# MAIN.net
KiCad netlist of a schematic drawn in Altium Designer
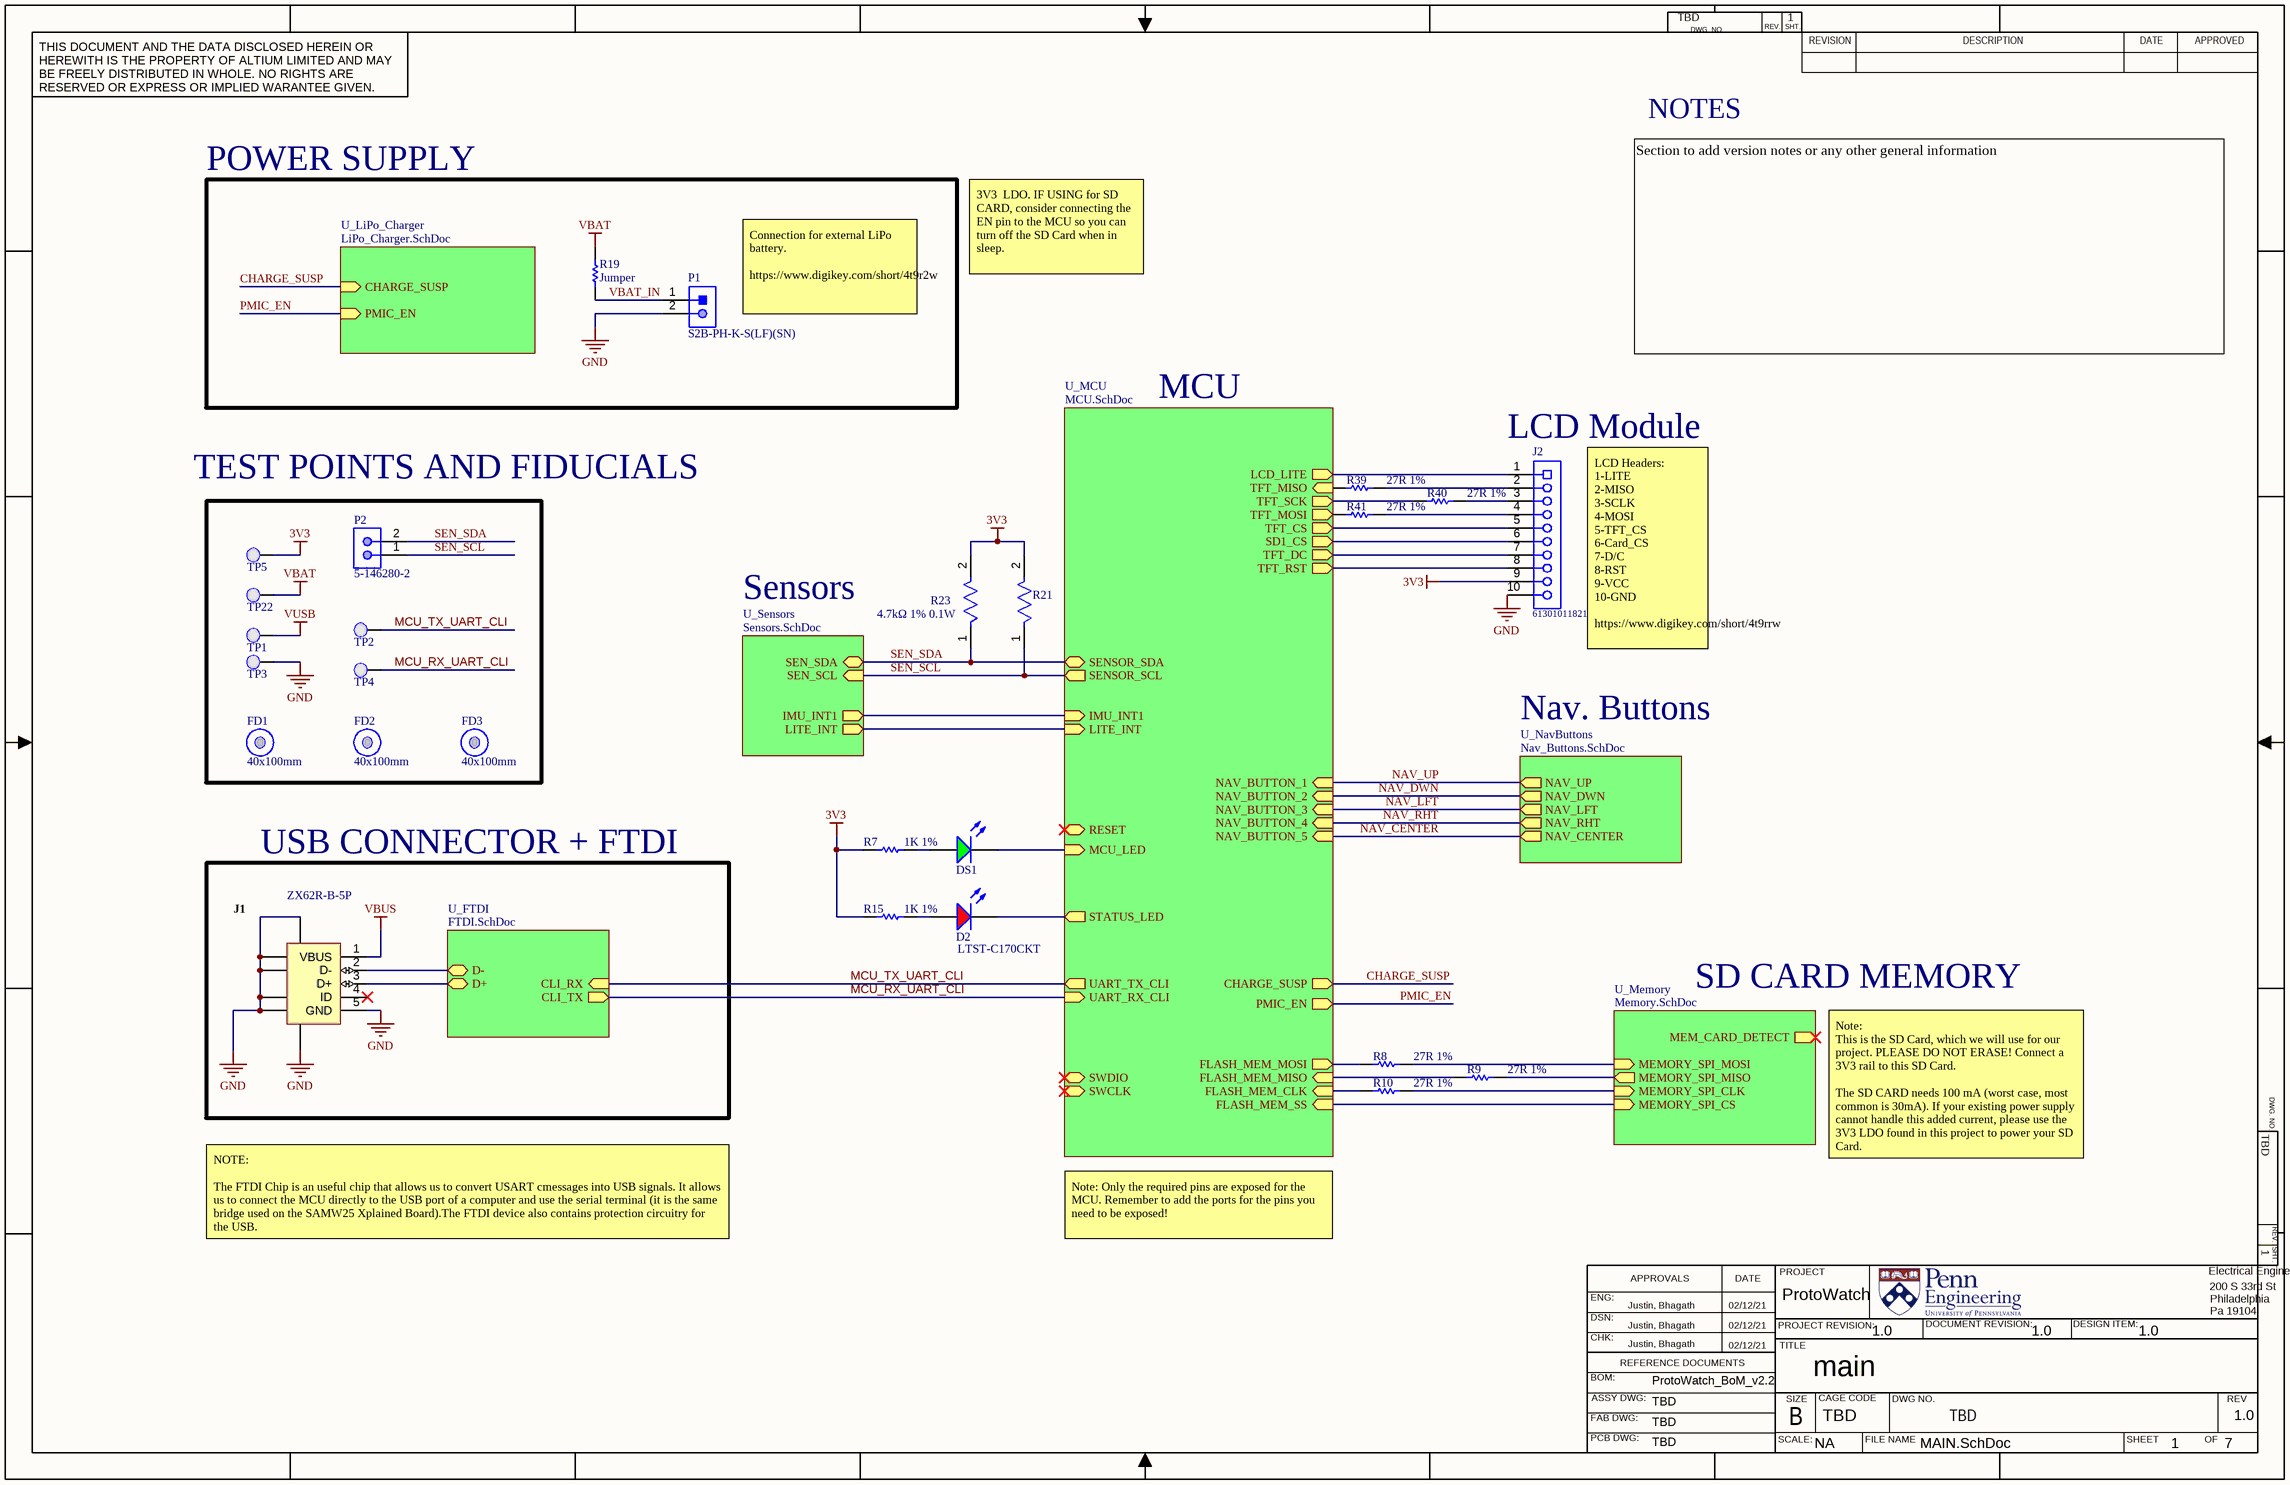
[diagram p0: MAIN.SchDoc]

(export (version "E")
  (design (tool "Eeschema 10.0.6"))
  (components
    (comp (ref "D2")
      (value "LTST-C170CKT")
      (footprint "LTST-C170CKT_V")
      (description "LED Uni-Color Red, 100 mW, 200 mA, -55 to 85 degC, 2-Pin SMD, RoHS, Tape and Reel")
      (fields (field (name "MANUFACTURER") "Lite-On"))
      (libsource (lib "Altium Content Vault") (part "LED-RED-AK-2"))
    )
    (comp (ref "DS1")
      (value "LTST-C170GKT")
      (footprint "LTST-C170GKT_V")
      (description "LED Uni-Color Green, 100 mW, 120 mA, -55 to 85 degC, 2-Pin SMD, RoHS, Tape and Reel")
      (fields (field (name "MANUFACTURER") "Lite-On"))
      (libsource (lib "Altium Content Vault") (part "LED-GREEN-AK-2"))
    )
    (comp (ref "FD1")
      (value "40x100mm")
      (footprint "Fiducial_FT")
      (description "Fiducial 40x100mm")
      (libsource (lib "Components - 01.02.21 - 21.11") (part "CMP-00174-A.4"))
    )
    (comp (ref "FD2")
      (value "40x100mm")
      (footprint "Fiducial_FT")
      (description "Fiducial 40x100mm")
      (libsource (lib "Components - 01.02.21 - 21.11") (part "CMP-00174-A.4"))
    )
    (comp (ref "FD3")
      (value "40x100mm")
      (footprint "Fiducial_FT")
      (description "Fiducial 40x100mm")
      (libsource (lib "Components - 01.02.21 - 21.11") (part "CMP-00174-A.4"))
    )
    (comp (ref "J1")
      (value "ZX62R-B-5P")
      (footprint "HIRO-ZX62R-B-5P_V")
      (description "Connector; USBMicro-B,Reverse type, SMT; 5 Position; Right Angle")
      (libsource (lib "Altium Content Vault") (part "HIRO-ZX62R-B-5P-5"))
    )
    (comp (ref "J2")
      (value "61301011821")
      (footprint "61301011821")
      (description "THT Vertical Socket Header WR-PHD, Pitch 2.54 mm, Single Row, 10 pins")
      (fields (field (name "MANUFACTURER") "Wurth Elektronik") (field (name "PUBLISHER") "WurthElektronik"))
      (libsource (lib "Altium Content Vault") (part "WE-CN-1P-F-R10"))
    )
    (comp (ref "P1")
      (value "S2B-PH-K-S(LF)(SN)")
      (footprint "JST-S2B-PH-K-S_V")
      (fields (field (name "TOLERANCE") "20%"))
      (libsource (lib "Altium Content Vault") (part "CN-1P-M-R2"))
    )
    (comp (ref "P2")
      (value "5-146280-2")
      (footprint "TECO-5-146280-2_V")
      (fields (field (name "MANUFACTURER") "TE Connectivity"))
      (libsource (lib "") (part "CN-1P-M-R2_1"))
    )
    (comp (ref "R7")
      (value "1K 1%")
      (footprint "RESC0603(1608)_N")
      (description "1K 0.1W 1% 0603 (1608 Metric)  SMD")
      (fields (field (name "TOLERANCE") "1 %") (field (name "POWER") "0.1 W"))
      (libsource (lib "Altium Content Vault") (part "RES"))
    )
    (comp (ref "R8")
      (value "27R 1%")
      (footprint "RESC0603(1608)_N")
      (description "27R 0.1W 1% 0603 (1608 Metric)  SMD")
      (fields (field (name "TOLERANCE") "1 %") (field (name "POWER") "0.1 W"))
      (libsource (lib "Altium Content Vault") (part "RES"))
    )
    (comp (ref "R9")
      (value "27R 1%")
      (footprint "RESC0603(1608)_N")
      (description "27R 0.1W 1% 0603 (1608 Metric)  SMD")
      (fields (field (name "TOLERANCE") "1 %") (field (name "POWER") "0.1 W"))
      (libsource (lib "Altium Content Vault") (part "RES"))
    )
    (comp (ref "R10")
      (value "27R 1%")
      (footprint "RESC0603(1608)_N")
      (description "27R 0.1W 1% 0603 (1608 Metric)  SMD")
      (fields (field (name "TOLERANCE") "1 %") (field (name "POWER") "0.1 W"))
      (libsource (lib "Altium Content Vault") (part "RES"))
    )
    (comp (ref "R15")
      (value "1K 1%")
      (footprint "RESC0603(1608)_N")
      (description "1K 0.1W 1% 0603 (1608 Metric)  SMD")
      (fields (field (name "TOLERANCE") "1 %") (field (name "POWER") "0.1 W"))
      (libsource (lib "Altium Content Vault") (part "RES"))
    )
    (comp (ref "R19")
      (value "Jumper")
      (footprint "RESC0603(1608)_N")
      (description "Jumper 0603 (1608 Metric)")
      (fields (field (name "POWER") "None"))
      (libsource (lib "Altium Content Vault") (part "RES"))
    )
    (comp (ref "R21")
      (value "4.7kΩ 1% 0.1W")
      (footprint "FP-RC1608-IPC_B")
      (description "Res Thick Film 0603 4.7kΩ 1% 0.1W ±100ppm/°C Molded SMD T/R RC1608F472AS")
      (fields (field (name "TOLERANCE") "1%"))
      (libsource (lib "Altium Content Vault") (part "1029c3af85768c4190bb7ad29bc67b5"))
    )
    (comp (ref "R23")
      (value "4.7kΩ 1% 0.1W")
      (footprint "FP-RC1608-IPC_B")
      (description "Res Thick Film 0603 4.7kΩ 1% 0.1W ±100ppm/°C Molded SMD T/R RC1608F472AS")
      (fields (field (name "TOLERANCE") "1%"))
      (libsource (lib "Altium Content Vault") (part "1029c3af85768c4190bb7ad29bc67b5"))
    )
    (comp (ref "R39")
      (value "27R 1%")
      (footprint "RESC0603(1608)_N")
      (description "27R 0.1W 1% 0603 (1608 Metric)  SMD")
      (fields (field (name "TOLERANCE") "1 %") (field (name "POWER") "0.1 W"))
      (libsource (lib "Altium Content Vault") (part "RES"))
    )
    (comp (ref "R40")
      (value "27R 1%")
      (footprint "RESC0603(1608)_N")
      (description "27R 0.1W 1% 0603 (1608 Metric)  SMD")
      (fields (field (name "TOLERANCE") "1 %") (field (name "POWER") "0.1 W"))
      (libsource (lib "Altium Content Vault") (part "RES"))
    )
    (comp (ref "R41")
      (value "27R 1%")
      (footprint "RESC0603(1608)_N")
      (description "27R 0.1W 1% 0603 (1608 Metric)  SMD")
      (fields (field (name "TOLERANCE") "1 %") (field (name "POWER") "0.1 W"))
      (libsource (lib "Altium Content Vault") (part "RES"))
    )
    (comp (ref "TP1")
      (value "0.1\" Pad")
      (footprint "PCBComponent")
      (libsource (lib "Components - 12.02.20 - 18.05") (part "0.1{dblquote} Pad-A.4"))
    )
    (comp (ref "TP2")
      (value "0.1\" Pad")
      (footprint "PCBComponent")
      (libsource (lib "Components - 12.02.20 - 18.05") (part "0.1{dblquote} Pad-A.4"))
    )
    (comp (ref "TP3")
      (value "0.1\" Pad")
      (footprint "PCBComponent")
      (libsource (lib "Components - 12.02.20 - 18.05") (part "0.1{dblquote} Pad-A.4"))
    )
    (comp (ref "TP4")
      (value "0.1\" Pad")
      (footprint "PCBComponent")
      (libsource (lib "Components - 12.02.20 - 18.05") (part "0.1{dblquote} Pad-A.4"))
    )
    (comp (ref "TP5")
      (value "0.1\" Pad")
      (footprint "PCBComponent")
      (libsource (lib "Components - 12.02.20 - 18.05") (part "0.1{dblquote} Pad-A.4"))
    )
    (comp (ref "TP22")
      (value "0.1\" Pad")
      (footprint "PCBComponent")
      (libsource (lib "Components - 12.02.20 - 18.05") (part "0.1{dblquote} Pad-A.4"))
    )
  )
  (nets
    (net (code "2") (name "/D+") (class "Default")
      (node (ref "J1") (pin "3") (pinfunction "D+_3") (pintype "bidirectional"))
    )
    (net (code "3") (name "/D-") (class "Default")
      (node (ref "J1") (pin "2") (pinfunction "D-_2") (pintype "bidirectional"))
    )
    (net (code "4") (name "/FLASH_MEM_CLK") (class "Default")
      (node (ref "R10") (pin "1") (pinfunction "1_1") (pintype "passive"))
    )
    (net (code "5") (name "/FLASH_MEM_MISO") (class "Default")
      (node (ref "R9") (pin "1") (pinfunction "1_1") (pintype "passive"))
    )
    (net (code "6") (name "/FLASH_MEM_MOSI") (class "Default")
      (node (ref "R8") (pin "1") (pinfunction "1_1") (pintype "passive"))
    )
    (net (code "9") (name "/LCD_LITE") (class "Default")
      (node (ref "J2") (pin "1") (pinfunction "1_1") (pintype "passive"))
    )
    (net (code "11") (name "/MCU_LED") (class "Default")
      (node (ref "DS1") (pin "2") (pinfunction "K_2") (pintype "passive"))
    )
    (net (code "12") (name "/MCU_RX_UART_CLI") (class "Default")
      (node (ref "TP4") (pin "1") (pinfunction "PAD_1") (pintype "passive"))
    )
    (net (code "13") (name "/MCU_TX_UART_CLI") (class "Default")
      (node (ref "TP2") (pin "1") (pinfunction "PAD_1") (pintype "passive"))
    )
    (net (code "14") (name "/MEMORY_SPI_CLK") (class "Default")
      (node (ref "R10") (pin "2") (pinfunction "2_2") (pintype "passive"))
    )
    (net (code "15") (name "/MEMORY_SPI_MISO") (class "Default")
      (node (ref "R9") (pin "2") (pinfunction "2_2") (pintype "passive"))
    )
    (net (code "16") (name "/MEMORY_SPI_MOSI") (class "Default")
      (node (ref "R8") (pin "2") (pinfunction "2_2") (pintype "passive"))
    )
    (net (code "25") (name "/SD1_CS") (class "Default")
      (node (ref "J2") (pin "6") (pinfunction "6_6") (pintype "passive"))
    )
    (net (code "26") (name "/SEN_SCL") (class "Default")
      (node (ref "P2") (pin "1") (pinfunction "1_1") (pintype "passive"))
      (node (ref "R21") (pin "1") (pinfunction "1_1") (pintype "passive"))
    )
    (net (code "27") (name "/SEN_SDA") (class "Default")
      (node (ref "P2") (pin "2") (pinfunction "2_2") (pintype "passive"))
      (node (ref "R23") (pin "1") (pinfunction "1_1") (pintype "passive"))
    )
    (net (code "28") (name "/STATUS_LED") (class "Default")
      (node (ref "D2") (pin "2") (pinfunction "K_2") (pintype "passive"))
    )
    (net (code "31") (name "/TFT_CS") (class "Default")
      (node (ref "J2") (pin "5") (pinfunction "5_5") (pintype "passive"))
    )
    (net (code "32") (name "/TFT_DC") (class "Default")
      (node (ref "J2") (pin "7") (pinfunction "7_7") (pintype "passive"))
    )
    (net (code "33") (name "/TFT_MISO") (class "Default")
      (node (ref "R39") (pin "1") (pinfunction "1_1") (pintype "passive"))
    )
    (net (code "34") (name "/TFT_MOSI") (class "Default")
      (node (ref "R41") (pin "1") (pinfunction "1_1") (pintype "passive"))
    )
    (net (code "35") (name "/TFT_RST") (class "Default")
      (node (ref "J2") (pin "8") (pinfunction "8_8") (pintype "passive"))
    )
    (net (code "36") (name "/TFT_SCK") (class "Default")
      (node (ref "R40") (pin "1") (pinfunction "1_1") (pintype "passive"))
    )
    (net (code "37") (name "/VBAT_IN") (class "Default")
      (node (ref "P1") (pin "1") (pinfunction "1_1") (pintype "passive"))
      (node (ref "R19") (pin "2") (pinfunction "2_2") (pintype "passive"))
    )
    (net (code "38") (name "3V3") (class "Default")
      (node (ref "J2") (pin "9") (pinfunction "9_9") (pintype "passive"))
      (node (ref "R15") (pin "1") (pinfunction "1_1") (pintype "passive"))
      (node (ref "R21") (pin "2") (pinfunction "2_2") (pintype "passive"))
      (node (ref "R23") (pin "2") (pinfunction "2_2") (pintype "passive"))
      (node (ref "R7") (pin "1") (pinfunction "1_1") (pintype "passive"))
      (node (ref "TP5") (pin "1") (pinfunction "PAD_1") (pintype "passive"))
    )
    (net (code "39") (name "GND") (class "Default")
      (node (ref "J1") (pin "10") (pinfunction "SHLD_10") (pintype "passive"))
      (node (ref "J1") (pin "11") (pinfunction "SHLD_11") (pintype "passive"))
      (node (ref "J1") (pin "5") (pinfunction "GND_5") (pintype "power_in"))
      (node (ref "J1") (pin "6") (pinfunction "SHLD_6") (pintype "passive"))
      (node (ref "J1") (pin "7") (pinfunction "SHLD_7") (pintype "passive"))
      (node (ref "J1") (pin "8") (pinfunction "SHLD_8") (pintype "passive"))
      (node (ref "J1") (pin "9") (pinfunction "SHLD_9") (pintype "passive"))
      (node (ref "J2") (pin "10") (pinfunction "10_10") (pintype "passive"))
      (node (ref "P1") (pin "2") (pinfunction "2_2") (pintype "passive"))
      (node (ref "TP3") (pin "1") (pinfunction "PAD_1") (pintype "passive"))
    )
    (net (code "40") (name "Net-(D2-A)") (class "Default")
      (node (ref "D2") (pin "1") (pinfunction "A_1") (pintype "passive"))
      (node (ref "R15") (pin "2") (pinfunction "2_2") (pintype "passive"))
    )
    (net (code "41") (name "Net-(DS1-A)") (class "Default")
      (node (ref "DS1") (pin "1") (pinfunction "A_1") (pintype "passive"))
      (node (ref "R7") (pin "2") (pinfunction "2_2") (pintype "passive"))
    )
    (net (code "42") (name "Net-(J2-Pad2)") (class "Default")
      (node (ref "J2") (pin "2") (pinfunction "2_2") (pintype "passive"))
      (node (ref "R39") (pin "2") (pinfunction "2_2") (pintype "passive"))
    )
    (net (code "43") (name "Net-(J2-Pad3)") (class "Default")
      (node (ref "J2") (pin "3") (pinfunction "3_3") (pintype "passive"))
      (node (ref "R40") (pin "2") (pinfunction "2_2") (pintype "passive"))
    )
    (net (code "44") (name "Net-(J2-Pad4)") (class "Default")
      (node (ref "J2") (pin "4") (pinfunction "4_4") (pintype "passive"))
      (node (ref "R41") (pin "2") (pinfunction "2_2") (pintype "passive"))
    )
    (net (code "45") (name "VBAT") (class "Default")
      (node (ref "R19") (pin "1") (pinfunction "1_1") (pintype "passive"))
      (node (ref "TP22") (pin "1") (pinfunction "PAD_1") (pintype "passive"))
    )
    (net (code "46") (name "VBUS") (class "Default")
      (node (ref "J1") (pin "1") (pinfunction "VBUS_1") (pintype "power_in"))
    )
    (net (code "47") (name "VUSB") (class "Default")
      (node (ref "TP1") (pin "1") (pinfunction "PAD_1") (pintype "passive"))
    )
    (net (code "48") (name "unconnected-(J1-ID-Pad4)") (class "Default")
      (node (ref "J1") (pin "4") (pinfunction "ID_4") (pintype "passive+no_connect"))
    )
  )
)
